# A3010_IDE.net
KiCad netlist of a schematic drawn in Altium Designer
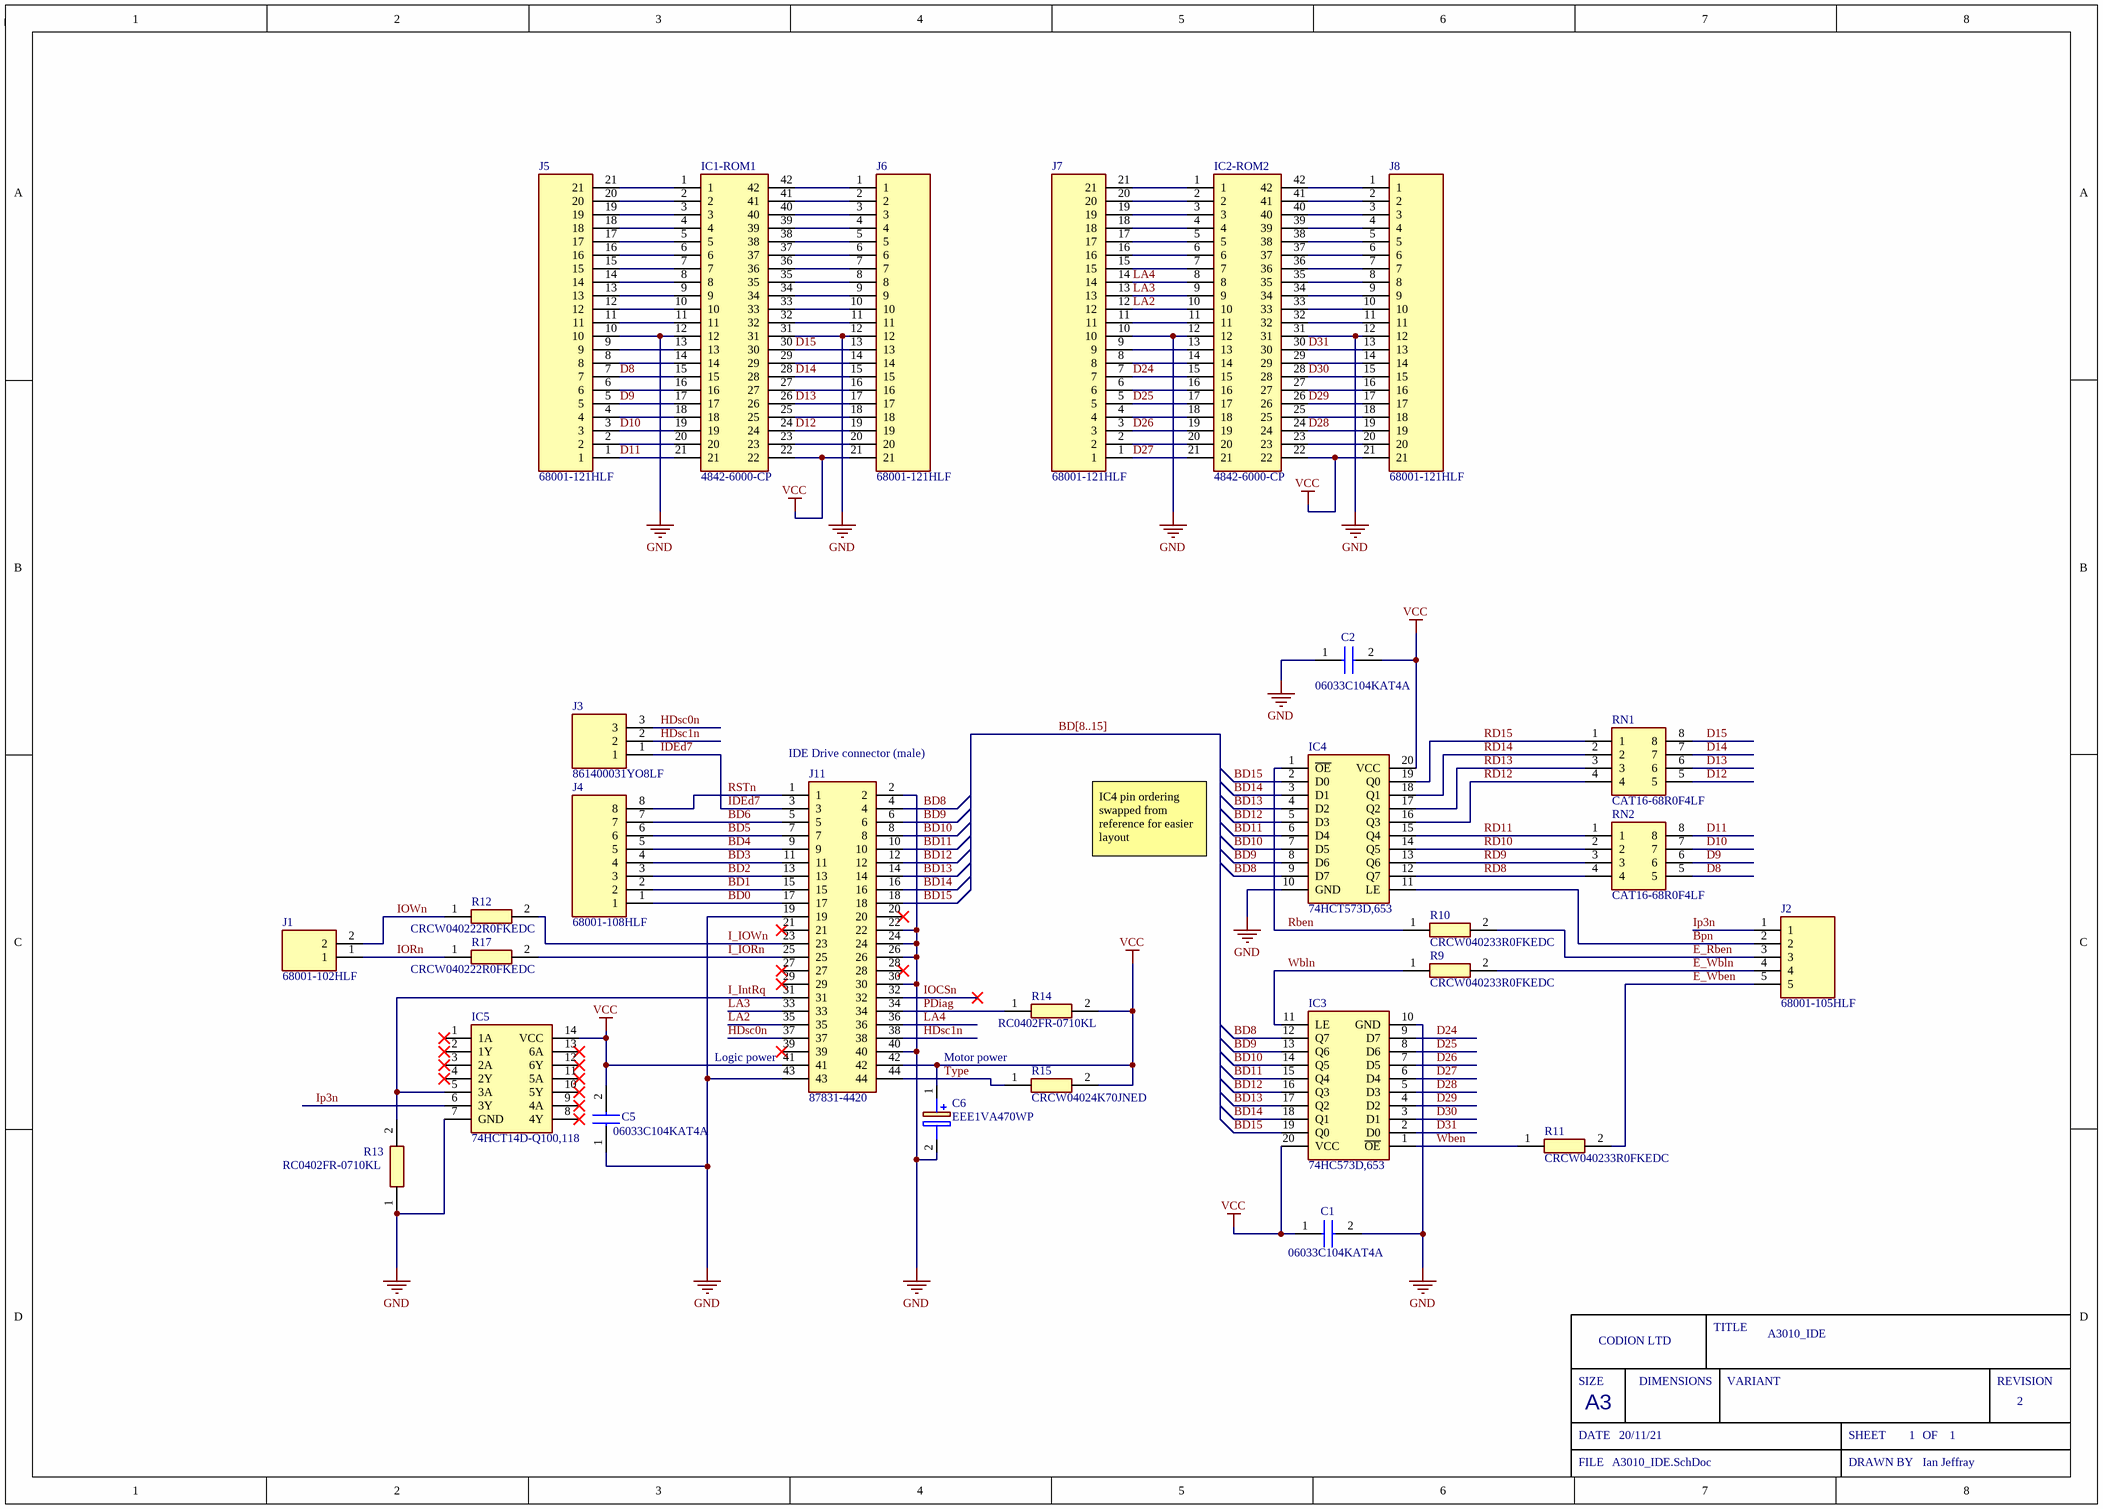
[diagram p0: A3010_IDE.SchDoc]

(export (version "E")
  (design (tool "Eeschema 10.0.6"))
  (components
    (comp (ref "C1")
      (value "06033C104KAT4A")
      (footprint "SamacSys:CAPC1608X90N")
      (description "Capacitor")
      (fields (field (name "MOUSER PART NUMBER") "581-06033C104KAT4A"))
      (libsource (lib "*") (part "06033C104KAT4A"))
    )
    (comp (ref "C2")
      (value "06033C104KAT4A")
      (footprint "SamacSys:CAPC1608X90N")
      (description "Capacitor")
      (fields (field (name "MOUSER PART NUMBER") "581-06033C104KAT4A"))
      (libsource (lib "*") (part "06033C104KAT4A"))
    )
    (comp (ref "C5")
      (value "06033C104KAT4A")
      (footprint "SamacSys:CAPC1608X90N")
      (description "Capacitor")
      (fields (field (name "MOUSER PART NUMBER") "581-06033C104KAT4A"))
      (libsource (lib "*") (part "06033C104KAT4A"))
    )
    (comp (ref "C6")
      (value "EEE1VA470WP")
      (footprint "SamacSys:EEE1AA101SP")
      (description "Capacitor Polarised")
      (libsource (lib "*") (part "EEE1VA470WP"))
    )
    (comp (ref "IC1-ROM1")
      (value "4842-6000-CP")
      (footprint "SamacSys:48426000CP")
      (description "Connector")
      (fields (field (name "MOUSER PART NUMBER") "517-4842-6000-CP"))
      (libsource (lib "*") (part "4842-6000-CP"))
    )
    (comp (ref "IC2-ROM2")
      (value "4842-6000-CP")
      (footprint "SamacSys:48426000CP")
      (description "Connector")
      (fields (field (name "MOUSER PART NUMBER") "517-4842-6000-CP"))
      (libsource (lib "*") (part "4842-6000-CP"))
    )
    (comp (ref "IC3")
      (value "74HC573D,653")
      (footprint "SamacSys:SOIC127P1032X265-20N")
      (description "Integrated Circuit")
      (fields (field (name "MOUSER PART NUMBER") "771-74HC573D-T"))
      (libsource (lib "*") (part "74HC573D,653"))
    )
    (comp (ref "IC4")
      (value "74HCT573D,653")
      (footprint "SamacSys:SOIC127P1032X265-20N")
      (description "Integrated Circuit")
      (fields (field (name "MOUSER PART NUMBER") "771-HCT573D653"))
      (libsource (lib "*") (part "74HCT573D,653"))
    )
    (comp (ref "IC5")
      (value "74HCT14D-Q100,118")
      (footprint "SamacSys:SOIC127P600X175-14N")
      (description "Integrated Circuit")
      (fields (field (name "MOUSER PART NUMBER") "771-74HCT14D-Q100118"))
      (libsource (lib "*") (part "74HCT14D-Q100,118"))
    )
    (comp (ref "J1")
      (value "68001-102HLF")
      (footprint "SamacSys:HDRV2W67P0X254_1X2_508X241X858P")
      (description "Connector")
      (fields (field (name "MOUSER PART NUMBER") "649-68001-102HLF"))
      (libsource (lib "*") (part "68001-102HLF"))
    )
    (comp (ref "J2")
      (value "68001-105HLF")
      (footprint "SamacSys:HDRV5W90P0X254_1X5_1270X241X1143P")
      (description "Connector")
      (fields (field (name "MOUSER PART NUMBER") "649-68001-105HLF"))
      (libsource (lib "*") (part "68001-105HLF"))
    )
    (comp (ref "J3")
      (value "861400031YO8LF")
      (footprint "SamacSys:HDRV3W63P0X254_1X3_762X254X980P")
      (description "Connector")
      (fields (field (name "MOUSER PART NUMBER") "649-861400031YO8LF"))
      (libsource (lib "*") (part "861400031YO8LF"))
    )
    (comp (ref "J4")
      (value "68001-108HLF")
      (footprint "SamacSys:HDRV8W90P0X254_1X8_2032X241X1143P")
      (description "Connector")
      (fields (field (name "MOUSER PART NUMBER") "649-68001-108HLF"))
      (libsource (lib "*") (part "68001-108HLF"))
    )
    (comp (ref "J5")
      (value "68001-121HLF")
      (footprint "SamacSys:HDRV21W67P0X254_1X21_5334X241X858P")
      (description "Connector")
      (fields (field (name "MOUSER PART NUMBER") "649-68001-121HLF"))
      (libsource (lib "*") (part "68001-121HLF"))
    )
    (comp (ref "J6")
      (value "68001-121HLF")
      (footprint "SamacSys:HDRV21W67P0X254_1X21_5334X241X858P")
      (description "Connector")
      (fields (field (name "MOUSER PART NUMBER") "649-68001-121HLF"))
      (libsource (lib "") (part "68001-121HLF_1"))
    )
    (comp (ref "J7")
      (value "68001-121HLF")
      (footprint "SamacSys:HDRV21W67P0X254_1X21_5334X241X858P")
      (description "Connector")
      (fields (field (name "MOUSER PART NUMBER") "649-68001-121HLF"))
      (libsource (lib "*") (part "68001-121HLF"))
    )
    (comp (ref "J8")
      (value "68001-121HLF")
      (footprint "SamacSys:HDRV21W67P0X254_1X21_5334X241X858P")
      (description "Connector")
      (fields (field (name "MOUSER PART NUMBER") "649-68001-121HLF"))
      (libsource (lib "") (part "68001-121HLF_1"))
    )
    (comp (ref "J11")
      (value "87831-4420")
      (footprint "SamacSys:SHDR44W55P200_2X22_4665X630X640P")
      (description "Connector")
      (fields (field (name "MOUSER PART NUMBER") "538-87831-4420"))
      (libsource (lib "*") (part "87831-4420"))
    )
    (comp (ref "R9")
      (value "CRCW040233R0FKEDC")
      (footprint "SamacSys:RESC1005X35N")
      (description "Resistor")
      (fields (field (name "MOUSER PART NUMBER") "71-CRCW040233R0FKEDC"))
      (libsource (lib "*") (part "CRCW040233R0FKEDC"))
    )
    (comp (ref "R10")
      (value "CRCW040233R0FKEDC")
      (footprint "SamacSys:RESC1005X35N")
      (description "Resistor")
      (fields (field (name "MOUSER PART NUMBER") "71-CRCW040233R0FKEDC"))
      (libsource (lib "*") (part "CRCW040233R0FKEDC"))
    )
    (comp (ref "R11")
      (value "CRCW040233R0FKEDC")
      (footprint "SamacSys:RESC1005X35N")
      (description "Resistor")
      (fields (field (name "MOUSER PART NUMBER") "71-CRCW040233R0FKEDC"))
      (libsource (lib "*") (part "CRCW040233R0FKEDC"))
    )
    (comp (ref "R12")
      (value "CRCW040222R0FKEDC")
      (footprint "SamacSys:RESC1005X35N")
      (description "Resistor")
      (fields (field (name "MOUSER PART NUMBER") "71-CRCW040222R0FKEDC"))
      (libsource (lib "*") (part "CRCW040222R0FKEDC"))
    )
    (comp (ref "R13")
      (value "RC0402FR-0710KL")
      (footprint "SamacSys:RESC1005X40N")
      (description "Resistor")
      (fields (field (name "MOUSER PART NUMBER") "603-RC0402FR-0710KL"))
      (libsource (lib "") (part "RC0402FR-0710KL_1"))
    )
    (comp (ref "R14")
      (value "RC0402FR-0710KL")
      (footprint "SamacSys:RESC1005X40N")
      (description "Resistor")
      (fields (field (name "MOUSER PART NUMBER") "603-RC0402FR-0710KL"))
      (libsource (lib "*") (part "RC0402FR-0710KL"))
    )
    (comp (ref "R15")
      (value "CRCW04024K70JNED")
      (footprint "SamacSys:RESC1005X40N")
      (description "Resistor")
      (fields (field (name "MOUSER PART NUMBER") "71-CRCW0402J-4.7K-E3"))
      (libsource (lib "*") (part "CRCW04024K70JNED"))
    )
    (comp (ref "R17")
      (value "CRCW040222R0FKEDC")
      (footprint "SamacSys:RESC1005X35N")
      (description "Resistor")
      (fields (field (name "MOUSER PART NUMBER") "71-CRCW040222R0FKEDC"))
      (libsource (lib "*") (part "CRCW040222R0FKEDC"))
    )
    (comp (ref "RN1")
      (value "CAT16-68R0F4LF")
      (footprint "SamacSys:CAT1668R0F4LF")
      (description "Resistor Network")
      (fields (field (name "MOUSER PART NUMBER") "652-CAT16-68R0F4LF"))
      (libsource (lib "*") (part "CAT16-68R0F4LF"))
    )
    (comp (ref "RN2")
      (value "CAT16-68R0F4LF")
      (footprint "SamacSys:CAT1668R0F4LF")
      (description "Resistor Network")
      (fields (field (name "MOUSER PART NUMBER") "652-CAT16-68R0F4LF"))
      (libsource (lib "*") (part "CAT16-68R0F4LF"))
    )
  )
  (nets
    (net (code "1") (name "/BD0") (class "Default")
      (node (ref "J11") (pin "17") (pinfunction "17_17") (pintype "passive"))
      (node (ref "J4") (pin "1") (pinfunction "1_1") (pintype "passive"))
    )
    (net (code "2") (name "/BD1") (class "Default")
      (node (ref "J11") (pin "15") (pinfunction "15_15") (pintype "passive"))
      (node (ref "J4") (pin "2") (pinfunction "2_2") (pintype "passive"))
    )
    (net (code "3") (name "/BD2") (class "Default")
      (node (ref "J11") (pin "13") (pinfunction "13_13") (pintype "passive"))
      (node (ref "J4") (pin "3") (pinfunction "3_3") (pintype "passive"))
    )
    (net (code "4") (name "/BD3") (class "Default")
      (node (ref "J11") (pin "11") (pinfunction "11_11") (pintype "passive"))
      (node (ref "J4") (pin "4") (pinfunction "4_4") (pintype "passive"))
    )
    (net (code "5") (name "/BD4") (class "Default")
      (node (ref "J11") (pin "9") (pinfunction "9_9") (pintype "passive"))
      (node (ref "J4") (pin "5") (pinfunction "5_5") (pintype "passive"))
    )
    (net (code "6") (name "/BD5") (class "Default")
      (node (ref "J11") (pin "7") (pinfunction "7_7") (pintype "passive"))
      (node (ref "J4") (pin "6") (pinfunction "6_6") (pintype "passive"))
    )
    (net (code "7") (name "/BD6") (class "Default")
      (node (ref "J11") (pin "5") (pinfunction "5_5") (pintype "passive"))
      (node (ref "J4") (pin "7") (pinfunction "7_7") (pintype "passive"))
    )
    (net (code "8") (name "/BD8") (class "Default")
      (node (ref "IC3") (pin "12") (pinfunction "Q7_12") (pintype "passive"))
      (node (ref "IC4") (pin "9") (pinfunction "D7_9") (pintype "passive"))
      (node (ref "J11") (pin "4") (pinfunction "4_4") (pintype "passive"))
    )
    (net (code "9") (name "/BD9") (class "Default")
      (node (ref "IC3") (pin "13") (pinfunction "Q6_13") (pintype "passive"))
      (node (ref "IC4") (pin "8") (pinfunction "D6_8") (pintype "passive"))
      (node (ref "J11") (pin "6") (pinfunction "6_6") (pintype "passive"))
    )
    (net (code "10") (name "/BD10") (class "Default")
      (node (ref "IC3") (pin "14") (pinfunction "Q5_14") (pintype "passive"))
      (node (ref "IC4") (pin "7") (pinfunction "D5_7") (pintype "passive"))
      (node (ref "J11") (pin "8") (pinfunction "8_8") (pintype "passive"))
    )
    (net (code "11") (name "/BD11") (class "Default")
      (node (ref "IC3") (pin "15") (pinfunction "Q4_15") (pintype "passive"))
      (node (ref "IC4") (pin "6") (pinfunction "D4_6") (pintype "passive"))
      (node (ref "J11") (pin "10") (pinfunction "10_10") (pintype "passive"))
    )
    (net (code "12") (name "/BD12") (class "Default")
      (node (ref "IC3") (pin "16") (pinfunction "Q3_16") (pintype "passive"))
      (node (ref "IC4") (pin "5") (pinfunction "D3_5") (pintype "passive"))
      (node (ref "J11") (pin "12") (pinfunction "12_12") (pintype "passive"))
    )
    (net (code "13") (name "/BD13") (class "Default")
      (node (ref "IC3") (pin "17") (pinfunction "Q2_17") (pintype "passive"))
      (node (ref "IC4") (pin "4") (pinfunction "D2_4") (pintype "passive"))
      (node (ref "J11") (pin "14") (pinfunction "14_14") (pintype "passive"))
    )
    (net (code "14") (name "/BD14") (class "Default")
      (node (ref "IC3") (pin "18") (pinfunction "Q1_18") (pintype "passive"))
      (node (ref "IC4") (pin "3") (pinfunction "D1_3") (pintype "passive"))
      (node (ref "J11") (pin "16") (pinfunction "16_16") (pintype "passive"))
    )
    (net (code "15") (name "/BD15") (class "Default")
      (node (ref "IC3") (pin "19") (pinfunction "Q0_19") (pintype "passive"))
      (node (ref "IC4") (pin "2") (pinfunction "D0_2") (pintype "passive"))
      (node (ref "J11") (pin "18") (pinfunction "18_18") (pintype "passive"))
    )
    (net (code "17") (name "/Bpn") (class "Default")
      (node (ref "IC4") (pin "11") (pinfunction "LE_11") (pintype "passive"))
      (node (ref "J2") (pin "2") (pinfunction "2_2") (pintype "passive"))
    )
    (net (code "18") (name "/D8") (class "Default")
      (node (ref "IC1-ROM1") (pin "15") (pinfunction "15_15") (pintype "passive"))
      (node (ref "J5") (pin "7") (pinfunction "7_7") (pintype "passive"))
      (node (ref "RN2") (pin "5") (pinfunction "5_5") (pintype "passive"))
    )
    (net (code "19") (name "/D9") (class "Default")
      (node (ref "IC1-ROM1") (pin "17") (pinfunction "17_17") (pintype "passive"))
      (node (ref "J5") (pin "5") (pinfunction "5_5") (pintype "passive"))
      (node (ref "RN2") (pin "6") (pinfunction "6_6") (pintype "passive"))
    )
    (net (code "20") (name "/D10") (class "Default")
      (node (ref "IC1-ROM1") (pin "19") (pinfunction "19_19") (pintype "passive"))
      (node (ref "J5") (pin "3") (pinfunction "3_3") (pintype "passive"))
      (node (ref "RN2") (pin "7") (pinfunction "7_7") (pintype "passive"))
    )
    (net (code "21") (name "/D11") (class "Default")
      (node (ref "IC1-ROM1") (pin "21") (pinfunction "21_21") (pintype "passive"))
      (node (ref "J5") (pin "1") (pinfunction "1_1") (pintype "passive"))
      (node (ref "RN2") (pin "8") (pinfunction "8_8") (pintype "passive"))
    )
    (net (code "22") (name "/D12") (class "Default")
      (node (ref "IC1-ROM1") (pin "24") (pinfunction "24_24") (pintype "passive"))
      (node (ref "J6") (pin "19") (pinfunction "19_19") (pintype "passive"))
      (node (ref "RN1") (pin "5") (pinfunction "5_5") (pintype "passive"))
    )
    (net (code "23") (name "/D13") (class "Default")
      (node (ref "IC1-ROM1") (pin "26") (pinfunction "26_26") (pintype "passive"))
      (node (ref "J6") (pin "17") (pinfunction "17_17") (pintype "passive"))
      (node (ref "RN1") (pin "6") (pinfunction "6_6") (pintype "passive"))
    )
    (net (code "24") (name "/D14") (class "Default")
      (node (ref "IC1-ROM1") (pin "28") (pinfunction "28_28") (pintype "passive"))
      (node (ref "J6") (pin "15") (pinfunction "15_15") (pintype "passive"))
      (node (ref "RN1") (pin "7") (pinfunction "7_7") (pintype "passive"))
    )
    (net (code "25") (name "/D15") (class "Default")
      (node (ref "IC1-ROM1") (pin "30") (pinfunction "30_30") (pintype "passive"))
      (node (ref "J6") (pin "13") (pinfunction "13_13") (pintype "passive"))
      (node (ref "RN1") (pin "8") (pinfunction "8_8") (pintype "passive"))
    )
    (net (code "26") (name "/D24") (class "Default")
      (node (ref "IC2-ROM2") (pin "15") (pinfunction "15_15") (pintype "passive"))
      (node (ref "IC3") (pin "9") (pinfunction "D7_9") (pintype "passive"))
      (node (ref "J7") (pin "7") (pinfunction "7_7") (pintype "passive"))
    )
    (net (code "27") (name "/D25") (class "Default")
      (node (ref "IC2-ROM2") (pin "17") (pinfunction "17_17") (pintype "passive"))
      (node (ref "IC3") (pin "8") (pinfunction "D6_8") (pintype "passive"))
      (node (ref "J7") (pin "5") (pinfunction "5_5") (pintype "passive"))
    )
    (net (code "28") (name "/D26") (class "Default")
      (node (ref "IC2-ROM2") (pin "19") (pinfunction "19_19") (pintype "passive"))
      (node (ref "IC3") (pin "7") (pinfunction "D5_7") (pintype "passive"))
      (node (ref "J7") (pin "3") (pinfunction "3_3") (pintype "passive"))
    )
    (net (code "29") (name "/D27") (class "Default")
      (node (ref "IC2-ROM2") (pin "21") (pinfunction "21_21") (pintype "passive"))
      (node (ref "IC3") (pin "6") (pinfunction "D4_6") (pintype "passive"))
      (node (ref "J7") (pin "1") (pinfunction "1_1") (pintype "passive"))
    )
    (net (code "30") (name "/D28") (class "Default")
      (node (ref "IC2-ROM2") (pin "24") (pinfunction "24_24") (pintype "passive"))
      (node (ref "IC3") (pin "5") (pinfunction "D3_5") (pintype "passive"))
      (node (ref "J8") (pin "19") (pinfunction "19_19") (pintype "passive"))
    )
    (net (code "31") (name "/D29") (class "Default")
      (node (ref "IC2-ROM2") (pin "26") (pinfunction "26_26") (pintype "passive"))
      (node (ref "IC3") (pin "4") (pinfunction "D2_4") (pintype "passive"))
      (node (ref "J8") (pin "17") (pinfunction "17_17") (pintype "passive"))
    )
    (net (code "32") (name "/D30") (class "Default")
      (node (ref "IC2-ROM2") (pin "28") (pinfunction "28_28") (pintype "passive"))
      (node (ref "IC3") (pin "3") (pinfunction "D1_3") (pintype "passive"))
      (node (ref "J8") (pin "15") (pinfunction "15_15") (pintype "passive"))
    )
    (net (code "33") (name "/D31") (class "Default")
      (node (ref "IC2-ROM2") (pin "30") (pinfunction "30_30") (pintype "passive"))
      (node (ref "IC3") (pin "2") (pinfunction "D0_2") (pintype "passive"))
      (node (ref "J8") (pin "13") (pinfunction "13_13") (pintype "passive"))
    )
    (net (code "34") (name "/E_Rben") (class "Default")
      (node (ref "J2") (pin "3") (pinfunction "3_3") (pintype "passive"))
      (node (ref "R10") (pin "2") (pinfunction "2_2") (pintype "passive"))
    )
    (net (code "35") (name "/E_Wben") (class "Default")
      (node (ref "J2") (pin "5") (pinfunction "5_5") (pintype "passive"))
      (node (ref "R11") (pin "2") (pinfunction "2_2") (pintype "passive"))
    )
    (net (code "36") (name "/E_Wbln") (class "Default")
      (node (ref "J2") (pin "4") (pinfunction "4_4") (pintype "passive"))
      (node (ref "R9") (pin "2") (pinfunction "2_2") (pintype "passive"))
    )
    (net (code "37") (name "/HDsc0n") (class "Default")
      (node (ref "J11") (pin "37") (pinfunction "37_37") (pintype "passive"))
      (node (ref "J3") (pin "3") (pinfunction "3_3") (pintype "passive"))
    )
    (net (code "38") (name "/HDsc1n") (class "Default")
      (node (ref "J11") (pin "38") (pinfunction "38_38") (pintype "passive"))
      (node (ref "J3") (pin "2") (pinfunction "2_2") (pintype "passive"))
    )
    (net (code "39") (name "/IDEd7") (class "Default")
      (node (ref "J11") (pin "3") (pinfunction "3_3") (pintype "passive"))
      (node (ref "J3") (pin "1") (pinfunction "1_1") (pintype "passive"))
    )
    (net (code "40") (name "/IOCSn") (class "Default")
      (node (ref "J11") (pin "32") (pinfunction "32_32") (pintype "passive+no_connect"))
    )
    (net (code "41") (name "/IORn") (class "Default")
      (node (ref "J1") (pin "1") (pinfunction "1_1") (pintype "passive"))
      (node (ref "R17") (pin "1") (pinfunction "1_1") (pintype "passive"))
    )
    (net (code "42") (name "/IOWn") (class "Default")
      (node (ref "J1") (pin "2") (pinfunction "2_2") (pintype "passive"))
      (node (ref "R12") (pin "1") (pinfunction "1_1") (pintype "passive"))
    )
    (net (code "43") (name "/I_IORn") (class "Default")
      (node (ref "J11") (pin "25") (pinfunction "25_25") (pintype "passive"))
      (node (ref "R17") (pin "2") (pinfunction "2_2") (pintype "passive"))
    )
    (net (code "44") (name "/I_IOWn") (class "Default")
      (node (ref "J11") (pin "23") (pinfunction "23_23") (pintype "passive"))
      (node (ref "R12") (pin "2") (pinfunction "2_2") (pintype "passive"))
    )
    (net (code "45") (name "/I_IntRq") (class "Default")
      (node (ref "IC5") (pin "5") (pinfunction "3A_5") (pintype "passive"))
      (node (ref "J11") (pin "31") (pinfunction "31_31") (pintype "passive"))
      (node (ref "R13") (pin "2") (pinfunction "2_2") (pintype "passive"))
    )
    (net (code "46") (name "/Ip3n") (class "Default")
      (node (ref "IC5") (pin "6") (pinfunction "3Y_6") (pintype "passive"))
      (node (ref "J2") (pin "1") (pinfunction "1_1") (pintype "passive"))
    )
    (net (code "47") (name "/LA2") (class "Default")
      (node (ref "IC2-ROM2") (pin "10") (pinfunction "10_10") (pintype "passive"))
      (node (ref "J11") (pin "35") (pinfunction "35_35") (pintype "passive"))
      (node (ref "J7") (pin "12") (pinfunction "12_12") (pintype "passive"))
    )
    (net (code "48") (name "/LA3") (class "Default")
      (node (ref "IC2-ROM2") (pin "9") (pinfunction "9_9") (pintype "passive"))
      (node (ref "J11") (pin "33") (pinfunction "33_33") (pintype "passive"))
      (node (ref "J7") (pin "13") (pinfunction "13_13") (pintype "passive"))
    )
    (net (code "49") (name "/LA4") (class "Default")
      (node (ref "IC2-ROM2") (pin "8") (pinfunction "8_8") (pintype "passive"))
      (node (ref "J11") (pin "36") (pinfunction "36_36") (pintype "passive"))
      (node (ref "J7") (pin "14") (pinfunction "14_14") (pintype "passive"))
    )
    (net (code "50") (name "/PDiag") (class "Default")
      (node (ref "J11") (pin "34") (pinfunction "34_34") (pintype "passive"))
      (node (ref "R14") (pin "1") (pinfunction "1_1") (pintype "passive"))
    )
    (net (code "51") (name "/RD8") (class "Default")
      (node (ref "IC4") (pin "12") (pinfunction "Q7_12") (pintype "passive"))
      (node (ref "RN2") (pin "4") (pinfunction "4_4") (pintype "passive"))
    )
    (net (code "52") (name "/RD9") (class "Default")
      (node (ref "IC4") (pin "13") (pinfunction "Q6_13") (pintype "passive"))
      (node (ref "RN2") (pin "3") (pinfunction "3_3") (pintype "passive"))
    )
    (net (code "53") (name "/RD10") (class "Default")
      (node (ref "IC4") (pin "14") (pinfunction "Q5_14") (pintype "passive"))
      (node (ref "RN2") (pin "2") (pinfunction "2_2") (pintype "passive"))
    )
    (net (code "54") (name "/RD11") (class "Default")
      (node (ref "IC4") (pin "15") (pinfunction "Q4_15") (pintype "passive"))
      (node (ref "RN2") (pin "1") (pinfunction "1_1") (pintype "passive"))
    )
    (net (code "55") (name "/RD12") (class "Default")
      (node (ref "IC4") (pin "16") (pinfunction "Q3_16") (pintype "passive"))
      (node (ref "RN1") (pin "4") (pinfunction "4_4") (pintype "passive"))
    )
    (net (code "56") (name "/RD13") (class "Default")
      (node (ref "IC4") (pin "17") (pinfunction "Q2_17") (pintype "passive"))
      (node (ref "RN1") (pin "3") (pinfunction "3_3") (pintype "passive"))
    )
    (net (code "57") (name "/RD14") (class "Default")
      (node (ref "IC4") (pin "18") (pinfunction "Q1_18") (pintype "passive"))
      (node (ref "RN1") (pin "2") (pinfunction "2_2") (pintype "passive"))
    )
    (net (code "58") (name "/RD15") (class "Default")
      (node (ref "IC4") (pin "19") (pinfunction "Q0_19") (pintype "passive"))
      (node (ref "RN1") (pin "1") (pinfunction "1_1") (pintype "passive"))
    )
    (net (code "59") (name "/RSTn") (class "Default")
      (node (ref "J11") (pin "1") (pinfunction "1_1") (pintype "passive"))
      (node (ref "J4") (pin "8") (pinfunction "8_8") (pintype "passive"))
    )
    (net (code "60") (name "/Rben") (class "Default")
      (node (ref "IC4") (pin "1") (pinfunction "~{OE}_1") (pintype "passive"))
      (node (ref "R10") (pin "1") (pinfunction "1_1") (pintype "passive"))
    )
    (net (code "61") (name "/Type") (class "Default")
      (node (ref "J11") (pin "44") (pinfunction "44_44") (pintype "passive"))
      (node (ref "R15") (pin "1") (pinfunction "1_1") (pintype "passive"))
    )
    (net (code "62") (name "/Wben") (class "Default")
      (node (ref "IC3") (pin "1") (pinfunction "~{OE}_1") (pintype "passive"))
      (node (ref "R11") (pin "1") (pinfunction "1_1") (pintype "passive"))
    )
    (net (code "63") (name "/Wbln") (class "Default")
      (node (ref "IC3") (pin "11") (pinfunction "LE_11") (pintype "passive"))
      (node (ref "R9") (pin "1") (pinfunction "1_1") (pintype "passive"))
    )
    (net (code "64") (name "GND") (class "Default")
      (node (ref "C1") (pin "2") (pinfunction "2_2") (pintype "passive"))
      (node (ref "C2") (pin "1") (pinfunction "1_1") (pintype "passive"))
      (node (ref "C5") (pin "1") (pinfunction "1_1") (pintype "passive"))
      (node (ref "C6") (pin "2") (pinfunction "-_2") (pintype "passive"))
      (node (ref "IC1-ROM1") (pin "12") (pinfunction "12_12") (pintype "passive"))
      (node (ref "IC1-ROM1") (pin "31") (pinfunction "31_31") (pintype "passive"))
      (node (ref "IC2-ROM2") (pin "12") (pinfunction "12_12") (pintype "passive"))
      (node (ref "IC2-ROM2") (pin "31") (pinfunction "31_31") (pintype "passive"))
      (node (ref "IC3") (pin "10") (pinfunction "GND_10") (pintype "passive"))
      (node (ref "IC4") (pin "10") (pinfunction "GND_10") (pintype "passive"))
      (node (ref "IC5") (pin "7") (pinfunction "GND_7") (pintype "passive"))
      (node (ref "J11") (pin "19") (pinfunction "19_19") (pintype "passive"))
      (node (ref "J11") (pin "2") (pinfunction "2_2") (pintype "passive"))
      (node (ref "J11") (pin "22") (pinfunction "22_22") (pintype "passive"))
      (node (ref "J11") (pin "24") (pinfunction "24_24") (pintype "passive"))
      (node (ref "J11") (pin "26") (pinfunction "26_26") (pintype "passive"))
      (node (ref "J11") (pin "30") (pinfunction "30_30") (pintype "passive"))
      (node (ref "J11") (pin "40") (pinfunction "40_40") (pintype "passive"))
      (node (ref "J11") (pin "43") (pinfunction "43_43") (pintype "passive"))
      (node (ref "J5") (pin "10") (pinfunction "10_10") (pintype "passive"))
      (node (ref "J6") (pin "12") (pinfunction "12_12") (pintype "passive"))
      (node (ref "J7") (pin "10") (pinfunction "10_10") (pintype "passive"))
      (node (ref "J8") (pin "12") (pinfunction "12_12") (pintype "passive"))
      (node (ref "R13") (pin "1") (pinfunction "1_1") (pintype "passive"))
    )
    (net (code "65") (name "Net-(IC1-ROM1-Pad1)") (class "Default")
      (node (ref "IC1-ROM1") (pin "1") (pinfunction "1_1") (pintype "passive"))
      (node (ref "J5") (pin "21") (pinfunction "21_21") (pintype "passive"))
    )
    (net (code "66") (name "Net-(IC1-ROM1-Pad2)") (class "Default")
      (node (ref "IC1-ROM1") (pin "2") (pinfunction "2_2") (pintype "passive"))
      (node (ref "J5") (pin "20") (pinfunction "20_20") (pintype "passive"))
    )
    (net (code "67") (name "Net-(IC1-ROM1-Pad3)") (class "Default")
      (node (ref "IC1-ROM1") (pin "3") (pinfunction "3_3") (pintype "passive"))
      (node (ref "J5") (pin "19") (pinfunction "19_19") (pintype "passive"))
    )
    (net (code "68") (name "Net-(IC1-ROM1-Pad4)") (class "Default")
      (node (ref "IC1-ROM1") (pin "4") (pinfunction "4_4") (pintype "passive"))
      (node (ref "J5") (pin "18") (pinfunction "18_18") (pintype "passive"))
    )
    (net (code "69") (name "Net-(IC1-ROM1-Pad5)") (class "Default")
      (node (ref "IC1-ROM1") (pin "5") (pinfunction "5_5") (pintype "passive"))
      (node (ref "J5") (pin "17") (pinfunction "17_17") (pintype "passive"))
    )
    (net (code "70") (name "Net-(IC1-ROM1-Pad6)") (class "Default")
      (node (ref "IC1-ROM1") (pin "6") (pinfunction "6_6") (pintype "passive"))
      (node (ref "J5") (pin "16") (pinfunction "16_16") (pintype "passive"))
    )
    (net (code "71") (name "Net-(IC1-ROM1-Pad7)") (class "Default")
      (node (ref "IC1-ROM1") (pin "7") (pinfunction "7_7") (pintype "passive"))
      (node (ref "J5") (pin "15") (pinfunction "15_15") (pintype "passive"))
    )
    (net (code "72") (name "Net-(IC1-ROM1-Pad8)") (class "Default")
      (node (ref "IC1-ROM1") (pin "8") (pinfunction "8_8") (pintype "passive"))
      (node (ref "J5") (pin "14") (pinfunction "14_14") (pintype "passive"))
    )
    (net (code "73") (name "Net-(IC1-ROM1-Pad9)") (class "Default")
      (node (ref "IC1-ROM1") (pin "9") (pinfunction "9_9") (pintype "passive"))
      (node (ref "J5") (pin "13") (pinfunction "13_13") (pintype "passive"))
    )
    (net (code "74") (name "Net-(IC1-ROM1-Pad10)") (class "Default")
      (node (ref "IC1-ROM1") (pin "10") (pinfunction "10_10") (pintype "passive"))
      (node (ref "J5") (pin "12") (pinfunction "12_12") (pintype "passive"))
    )
    (net (code "75") (name "Net-(IC1-ROM1-Pad11)") (class "Default")
      (node (ref "IC1-ROM1") (pin "11") (pinfunction "11_11") (pintype "passive"))
      (node (ref "J5") (pin "11") (pinfunction "11_11") (pintype "passive"))
    )
    (net (code "76") (name "Net-(IC1-ROM1-Pad13)") (class "Default")
      (node (ref "IC1-ROM1") (pin "13") (pinfunction "13_13") (pintype "passive"))
      (node (ref "J5") (pin "9") (pinfunction "9_9") (pintype "passive"))
    )
    (net (code "77") (name "Net-(IC1-ROM1-Pad14)") (class "Default")
      (node (ref "IC1-ROM1") (pin "14") (pinfunction "14_14") (pintype "passive"))
      (node (ref "J5") (pin "8") (pinfunction "8_8") (pintype "passive"))
    )
    (net (code "78") (name "Net-(IC1-ROM1-Pad16)") (class "Default")
      (node (ref "IC1-ROM1") (pin "16") (pinfunction "16_16") (pintype "passive"))
      (node (ref "J5") (pin "6") (pinfunction "6_6") (pintype "passive"))
    )
    (net (code "79") (name "Net-(IC1-ROM1-Pad18)") (class "Default")
      (node (ref "IC1-ROM1") (pin "18") (pinfunction "18_18") (pintype "passive"))
      (node (ref "J5") (pin "4") (pinfunction "4_4") (pintype "passive"))
    )
    (net (code "80") (name "Net-(IC1-ROM1-Pad20)") (class "Default")
      (node (ref "IC1-ROM1") (pin "20") (pinfunction "20_20") (pintype "passive"))
      (node (ref "J5") (pin "2") (pinfunction "2_2") (pintype "passive"))
    )
    (net (code "81") (name "Net-(IC1-ROM1-Pad23)") (class "Default")
      (node (ref "IC1-ROM1") (pin "23") (pinfunction "23_23") (pintype "passive"))
      (node (ref "J6") (pin "20") (pinfunction "20_20") (pintype "passive"))
    )
    (net (code "82") (name "Net-(IC1-ROM1-Pad25)") (class "Default")
      (node (ref "IC1-ROM1") (pin "25") (pinfunction "25_25") (pintype "passive"))
      (node (ref "J6") (pin "18") (pinfunction "18_18") (pintype "passive"))
    )
    (net (code "83") (name "Net-(IC1-ROM1-Pad27)") (class "Default")
      (node (ref "IC1-ROM1") (pin "27") (pinfunction "27_27") (pintype "passive"))
      (node (ref "J6") (pin "16") (pinfunction "16_16") (pintype "passive"))
    )
    (net (code "84") (name "Net-(IC1-ROM1-Pad29)") (class "Default")
      (node (ref "IC1-ROM1") (pin "29") (pinfunction "29_29") (pintype "passive"))
      (node (ref "J6") (pin "14") (pinfunction "14_14") (pintype "passive"))
    )
    (net (code "85") (name "Net-(IC1-ROM1-Pad32)") (class "Default")
      (node (ref "IC1-ROM1") (pin "32") (pinfunction "32_32") (pintype "passive"))
      (node (ref "J6") (pin "11") (pinfunction "11_11") (pintype "passive"))
    )
    (net (code "86") (name "Net-(IC1-ROM1-Pad33)") (class "Default")
      (node (ref "IC1-ROM1") (pin "33") (pinfunction "33_33") (pintype "passive"))
      (node (ref "J6") (pin "10") (pinfunction "10_10") (pintype "passive"))
    )
    (net (code "87") (name "Net-(IC1-ROM1-Pad34)") (class "Default")
      (node (ref "IC1-ROM1") (pin "34") (pinfunction "34_34") (pintype "passive"))
      (node (ref "J6") (pin "9") (pinfunction "9_9") (pintype "passive"))
    )
    (net (code "88") (name "Net-(IC1-ROM1-Pad35)") (class "Default")
      (node (ref "IC1-ROM1") (pin "35") (pinfunction "35_35") (pintype "passive"))
      (node (ref "J6") (pin "8") (pinfunction "8_8") (pintype "passive"))
    )
    (net (code "89") (name "Net-(IC1-ROM1-Pad36)") (class "Default")
      (node (ref "IC1-ROM1") (pin "36") (pinfunction "36_36") (pintype "passive"))
      (node (ref "J6") (pin "7") (pinfunction "7_7") (pintype "passive"))
    )
    (net (code "90") (name "Net-(IC1-ROM1-Pad37)") (class "Default")
      (node (ref "IC1-ROM1") (pin "37") (pinfunction "37_37") (pintype "passive"))
      (node (ref "J6") (pin "6") (pinfunction "6_6") (pintype "passive"))
    )
    (net (code "91") (name "Net-(IC1-ROM1-Pad38)") (class "Default")
      (node (ref "IC1-ROM1") (pin "38") (pinfunction "38_38") (pintype "passive"))
      (node (ref "J6") (pin "5") (pinfunction "5_5") (pintype "passive"))
    )
    (net (code "92") (name "Net-(IC1-ROM1-Pad39)") (class "Default")
      (node (ref "IC1-ROM1") (pin "39") (pinfunction "39_39") (pintype "passive"))
      (node (ref "J6") (pin "4") (pinfunction "4_4") (pintype "passive"))
    )
    (net (code "93") (name "Net-(IC1-ROM1-Pad40)") (class "Default")
      (node (ref "IC1-ROM1") (pin "40") (pinfunction "40_40") (pintype "passive"))
      (node (ref "J6") (pin "3") (pinfunction "3_3") (pintype "passive"))
    )
    (net (code "94") (name "Net-(IC1-ROM1-Pad41)") (class "Default")
      (node (ref "IC1-ROM1") (pin "41") (pinfunction "41_41") (pintype "passive"))
      (node (ref "J6") (pin "2") (pinfunction "2_2") (pintype "passive"))
    )
    (net (code "95") (name "Net-(IC1-ROM1-Pad42)") (class "Default")
      (node (ref "IC1-ROM1") (pin "42") (pinfunction "42_42") (pintype "passive"))
      (node (ref "J6") (pin "1") (pinfunction "1_1") (pintype "passive"))
    )
    (net (code "96") (name "Net-(IC2-ROM2-Pad1)") (class "Default")
      (node (ref "IC2-ROM2") (pin "1") (pinfunction "1_1") (pintype "passive"))
      (node (ref "J7") (pin "21") (pinfunction "21_21") (pintype "passive"))
    )
    (net (code "97") (name "Net-(IC2-ROM2-Pad2)") (class "Default")
      (node (ref "IC2-ROM2") (pin "2") (pinfunction "2_2") (pintype "passive"))
      (node (ref "J7") (pin "20") (pinfunction "20_20") (pintype "passive"))
    )
    (net (code "98") (name "Net-(IC2-ROM2-Pad3)") (class "Default")
      (node (ref "IC2-ROM2") (pin "3") (pinfunction "3_3") (pintype "passive"))
      (node (ref "J7") (pin "19") (pinfunction "19_19") (pintype "passive"))
    )
    (net (code "99") (name "Net-(IC2-ROM2-Pad4)") (class "Default")
      (node (ref "IC2-ROM2") (pin "4") (pinfunction "4_4") (pintype "passive"))
      (node (ref "J7") (pin "18") (pinfunction "18_18") (pintype "passive"))
    )
    (net (code "100") (name "Net-(IC2-ROM2-Pad5)") (class "Default")
      (node (ref "IC2-ROM2") (pin "5") (pinfunction "5_5") (pintype "passive"))
      (node (ref "J7") (pin "17") (pinfunction "17_17") (pintype "passive"))
    )
    (net (code "101") (name "Net-(IC2-ROM2-Pad6)") (class "Default")
      (node (ref "IC2-ROM2") (pin "6") (pinfunction "6_6") (pintype "passive"))
      (node (ref "J7") (pin "16") (pinfunction "16_16") (pintype "passive"))
    )
    (net (code "102") (name "Net-(IC2-ROM2-Pad7)") (class "Default")
      (node (ref "IC2-ROM2") (pin "7") (pinfunction "7_7") (pintype "passive"))
      (node (ref "J7") (pin "15") (pinfunction "15_15") (pintype "passive"))
    )
    (net (code "103") (name "Net-(IC2-ROM2-Pad11)") (class "Default")
      (node (ref "IC2-ROM2") (pin "11") (pinfunction "11_11") (pintype "passive"))
      (node (ref "J7") (pin "11") (pinfunction "11_11") (pintype "passive"))
    )
    (net (code "104") (name "Net-(IC2-ROM2-Pad13)") (class "Default")
      (node (ref "IC2-ROM2") (pin "13") (pinfunction "13_13") (pintype "passive"))
      (node (ref "J7") (pin "9") (pinfunction "9_9") (pintype "passive"))
    )
    (net (code "105") (name "Net-(IC2-ROM2-Pad14)") (class "Default")
      (node (ref "IC2-ROM2") (pin "14") (pinfunction "14_14") (pintype "passive"))
      (node (ref "J7") (pin "8") (pinfunction "8_8") (pintype "passive"))
    )
    (net (code "106") (name "Net-(IC2-ROM2-Pad16)") (class "Default")
      (node (ref "IC2-ROM2") (pin "16") (pinfunction "16_16") (pintype "passive"))
      (node (ref "J7") (pin "6") (pinfunction "6_6") (pintype "passive"))
    )
    (net (code "107") (name "Net-(IC2-ROM2-Pad18)") (class "Default")
      (node (ref "IC2-ROM2") (pin "18") (pinfunction "18_18") (pintype "passive"))
      (node (ref "J7") (pin "4") (pinfunction "4_4") (pintype "passive"))
    )
    (net (code "108") (name "Net-(IC2-ROM2-Pad20)") (class "Default")
      (node (ref "IC2-ROM2") (pin "20") (pinfunction "20_20") (pintype "passive"))
      (node (ref "J7") (pin "2") (pinfunction "2_2") (pintype "passive"))
    )
    (net (code "109") (name "Net-(IC2-ROM2-Pad23)") (class "Default")
      (node (ref "IC2-ROM2") (pin "23") (pinfunction "23_23") (pintype "passive"))
      (node (ref "J8") (pin "20") (pinfunction "20_20") (pintype "passive"))
    )
    (net (code "110") (name "Net-(IC2-ROM2-Pad25)") (class "Default")
      (node (ref "IC2-ROM2") (pin "25") (pinfunction "25_25") (pintype "passive"))
      (node (ref "J8") (pin "18") (pinfunction "18_18") (pintype "passive"))
    )
    (net (code "111") (name "Net-(IC2-ROM2-Pad27)") (class "Default")
      (node (ref "IC2-ROM2") (pin "27") (pinfunction "27_27") (pintype "passive"))
      (node (ref "J8") (pin "16") (pinfunction "16_16") (pintype "passive"))
    )
    (net (code "112") (name "Net-(IC2-ROM2-Pad29)") (class "Default")
      (node (ref "IC2-ROM2") (pin "29") (pinfunction "29_29") (pintype "passive"))
      (node (ref "J8") (pin "14") (pinfunction "14_14") (pintype "passive"))
    )
    (net (code "113") (name "Net-(IC2-ROM2-Pad32)") (class "Default")
      (node (ref "IC2-ROM2") (pin "32") (pinfunction "32_32") (pintype "passive"))
      (node (ref "J8") (pin "11") (pinfunction "11_11") (pintype "passive"))
    )
    (net (code "114") (name "Net-(IC2-ROM2-Pad33)") (class "Default")
      (node (ref "IC2-ROM2") (pin "33") (pinfunction "33_33") (pintype "passive"))
      (node (ref "J8") (pin "10") (pinfunction "10_10") (pintype "passive"))
    )
    (net (code "115") (name "Net-(IC2-ROM2-Pad34)") (class "Default")
      (node (ref "IC2-ROM2") (pin "34") (pinfunction "34_34") (pintype "passive"))
      (node (ref "J8") (pin "9") (pinfunction "9_9") (pintype "passive"))
    )
    (net (code "116") (name "Net-(IC2-ROM2-Pad35)") (class "Default")
      (node (ref "IC2-ROM2") (pin "35") (pinfunction "35_35") (pintype "passive"))
      (node (ref "J8") (pin "8") (pinfunction "8_8") (pintype "passive"))
    )
    (net (code "117") (name "Net-(IC2-ROM2-Pad36)") (class "Default")
      (node (ref "IC2-ROM2") (pin "36") (pinfunction "36_36") (pintype "passive"))
      (node (ref "J8") (pin "7") (pinfunction "7_7") (pintype "passive"))
    )
    (net (code "118") (name "Net-(IC2-ROM2-Pad37)") (class "Default")
      (node (ref "IC2-ROM2") (pin "37") (pinfunction "37_37") (pintype "passive"))
      (node (ref "J8") (pin "6") (pinfunction "6_6") (pintype "passive"))
    )
    (net (code "119") (name "Net-(IC2-ROM2-Pad38)") (class "Default")
      (node (ref "IC2-ROM2") (pin "38") (pinfunction "38_38") (pintype "passive"))
      (node (ref "J8") (pin "5") (pinfunction "5_5") (pintype "passive"))
    )
    (net (code "120") (name "Net-(IC2-ROM2-Pad39)") (class "Default")
      (node (ref "IC2-ROM2") (pin "39") (pinfunction "39_39") (pintype "passive"))
      (node (ref "J8") (pin "4") (pinfunction "4_4") (pintype "passive"))
    )
    (net (code "121") (name "Net-(IC2-ROM2-Pad40)") (class "Default")
      (node (ref "IC2-ROM2") (pin "40") (pinfunction "40_40") (pintype "passive"))
      (node (ref "J8") (pin "3") (pinfunction "3_3") (pintype "passive"))
    )
    (net (code "122") (name "Net-(IC2-ROM2-Pad41)") (class "Default")
      (node (ref "IC2-ROM2") (pin "41") (pinfunction "41_41") (pintype "passive"))
      (node (ref "J8") (pin "2") (pinfunction "2_2") (pintype "passive"))
    )
    (net (code "123") (name "Net-(IC2-ROM2-Pad42)") (class "Default")
      (node (ref "IC2-ROM2") (pin "42") (pinfunction "42_42") (pintype "passive"))
      (node (ref "J8") (pin "1") (pinfunction "1_1") (pintype "passive"))
    )
    (net (code "124") (name "VCC") (class "Default")
      (node (ref "C1") (pin "1") (pinfunction "1_1") (pintype "passive"))
      (node (ref "C2") (pin "2") (pinfunction "2_2") (pintype "passive"))
      (node (ref "C5") (pin "2") (pinfunction "2_2") (pintype "passive"))
      (node (ref "C6") (pin "1") (pinfunction "+_1") (pintype "passive"))
      (node (ref "IC1-ROM1") (pin "22") (pinfunction "22_22") (pintype "passive"))
      (node (ref "IC2-ROM2") (pin "22") (pinfunction "22_22") (pintype "passive"))
      (node (ref "IC3") (pin "20") (pinfunction "VCC_20") (pintype "passive"))
      (node (ref "IC4") (pin "20") (pinfunction "VCC_20") (pintype "passive"))
      (node (ref "IC5") (pin "14") (pinfunction "VCC_14") (pintype "passive"))
      (node (ref "J11") (pin "41") (pinfunction "41_41") (pintype "passive"))
      (node (ref "J11") (pin "42") (pinfunction "42_42") (pintype "passive"))
      (node (ref "J6") (pin "21") (pinfunction "21_21") (pintype "passive"))
      (node (ref "J8") (pin "21") (pinfunction "21_21") (pintype "passive"))
      (node (ref "R14") (pin "2") (pinfunction "2_2") (pintype "passive"))
      (node (ref "R15") (pin "2") (pinfunction "2_2") (pintype "passive"))
    )
    (net (code "125") (name "unconnected-(IC5-1A-Pad1)") (class "Default")
      (node (ref "IC5") (pin "1") (pinfunction "1A_1") (pintype "passive+no_connect"))
    )
    (net (code "126") (name "unconnected-(IC5-1Y-Pad2)") (class "Default")
      (node (ref "IC5") (pin "2") (pinfunction "1Y_2") (pintype "passive+no_connect"))
    )
    (net (code "127") (name "unconnected-(IC5-2A-Pad3)") (class "Default")
      (node (ref "IC5") (pin "3") (pinfunction "2A_3") (pintype "passive+no_connect"))
    )
    (net (code "128") (name "unconnected-(IC5-2Y-Pad4)") (class "Default")
      (node (ref "IC5") (pin "4") (pinfunction "2Y_4") (pintype "passive+no_connect"))
    )
    (net (code "129") (name "unconnected-(IC5-4A-Pad9)") (class "Default")
      (node (ref "IC5") (pin "9") (pinfunction "4A_9") (pintype "passive+no_connect"))
    )
    (net (code "130") (name "unconnected-(IC5-4Y-Pad8)") (class "Default")
      (node (ref "IC5") (pin "8") (pinfunction "4Y_8") (pintype "passive+no_connect"))
    )
    (net (code "131") (name "unconnected-(IC5-5A-Pad11)") (class "Default")
      (node (ref "IC5") (pin "11") (pinfunction "5A_11") (pintype "passive+no_connect"))
    )
    (net (code "132") (name "unconnected-(IC5-5Y-Pad10)") (class "Default")
      (node (ref "IC5") (pin "10") (pinfunction "5Y_10") (pintype "passive+no_connect"))
    )
    (net (code "133") (name "unconnected-(IC5-6A-Pad13)") (class "Default")
      (node (ref "IC5") (pin "13") (pinfunction "6A_13") (pintype "passive+no_connect"))
    )
    (net (code "134") (name "unconnected-(IC5-6Y-Pad12)") (class "Default")
      (node (ref "IC5") (pin "12") (pinfunction "6Y_12") (pintype "passive+no_connect"))
    )
    (net (code "135") (name "unconnected-(J11-Pad20)") (class "Default")
      (node (ref "J11") (pin "20") (pinfunction "20_20") (pintype "passive+no_connect"))
    )
    (net (code "136") (name "unconnected-(J11-Pad21)") (class "Default")
      (node (ref "J11") (pin "21") (pinfunction "21_21") (pintype "passive+no_connect"))
    )
    (net (code "137") (name "unconnected-(J11-Pad27)") (class "Default")
      (node (ref "J11") (pin "27") (pinfunction "27_27") (pintype "passive+no_connect"))
    )
    (net (code "138") (name "unconnected-(J11-Pad28)") (class "Default")
      (node (ref "J11") (pin "28") (pinfunction "28_28") (pintype "passive+no_connect"))
    )
    (net (code "139") (name "unconnected-(J11-Pad29)") (class "Default")
      (node (ref "J11") (pin "29") (pinfunction "29_29") (pintype "passive+no_connect"))
    )
    (net (code "140") (name "unconnected-(J11-Pad39)") (class "Default")
      (node (ref "J11") (pin "39") (pinfunction "39_39") (pintype "passive+no_connect"))
    )
  )
)
